# electrodePCB.net
KiCad netlist of a schematic drawn in Altium Designer
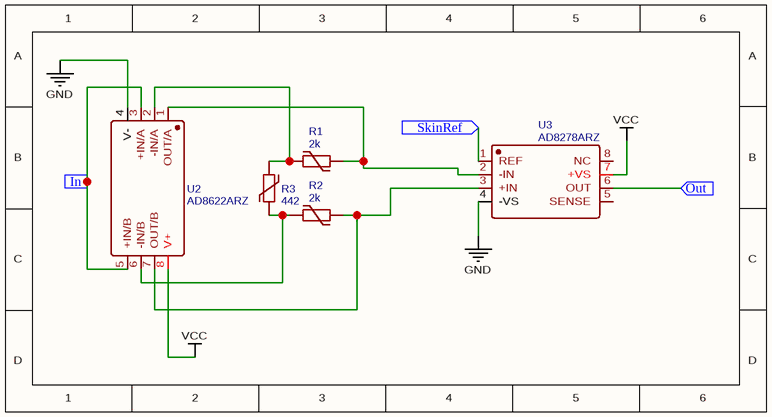
[diagram p0: electrodePCB.schdoc]

(export (version "E")
  (design (tool "Eeschema 10.0.6"))
  (components
    (comp (ref "R1")
      (value "2k")
      (fields
        (field (name "BOM_SUPPLIER PART") "C388274")
        (field (name "BOM_MANUFACTURER PART") "TCTR0402F100KF3950T")
        (field (name "CONTRIBUTOR") "LCSC")
      )
      (libsource (lib "altium-import") (part "root_0_2k_"))
    )
    (comp (ref "R2")
      (value "2k")
      (fields
        (field (name "BOM_SUPPLIER PART") "C388274")
        (field (name "BOM_MANUFACTURER PART") "TCTR0402F100KF3950T")
        (field (name "CONTRIBUTOR") "LCSC")
      )
      (libsource (lib "altium-import") (part "root_0_2k_"))
    )
    (comp (ref "R3")
      (value "442")
      (fields
        (field (name "BOM_SUPPLIER PART") "C388281")
        (field (name "BOM_MANUFACTURER PART") "TCTR0603F10K0F3980T")
        (field (name "CONTRIBUTOR") "LCSC")
      )
      (libsource (lib "altium-import") (part "root_1_442_"))
    )
    (comp (ref "U2")
      (value "AD8622ARZ")
      (fields (field (name "BOM_SUPPLIER PART") "C106970"))
      (libsource (lib "altium-import") (part "root_3_AD8622ARZ_"))
    )
    (comp (ref "U3")
      (value "AD8278ARZ")
      (fields (field (name "BOM_SUPPLIER PART") "C209371") (field (name "CONTRIBUTOR") "LCSC"))
      (libsource (lib "altium-import") (part "root_0_AD8278ARZ_"))
    )
  )
  (nets
    (net (code "1") (name "/In") (class "Default")
      (node (ref "U2") (pin "3") (pinfunction "+IN/A_3") (pintype "passive"))
      (node (ref "U2") (pin "5") (pinfunction "+IN/B_5") (pintype "passive"))
    )
    (net (code "2") (name "/Out") (class "Default")
      (node (ref "U3") (pin "6") (pinfunction "OUT_6") (pintype "passive"))
    )
    (net (code "3") (name "/SkinRef") (class "Default")
      (node (ref "U3") (pin "1") (pinfunction "REF_1") (pintype "passive"))
    )
    (net (code "4") (name "GND") (class "Default")
      (node (ref "U2") (pin "4") (pinfunction "V-_4") (pintype "passive"))
      (node (ref "U3") (pin "4") (pinfunction "-VS_4") (pintype "passive"))
    )
    (net (code "5") (name "Net-(U2--IN{slash}A)") (class "Default")
      (node (ref "R1") (pin "1") (pinfunction "1_1") (pintype "passive"))
      (node (ref "R3") (pin "2") (pinfunction "2_2") (pintype "passive"))
      (node (ref "U2") (pin "2") (pinfunction "-IN/A_2") (pintype "passive"))
    )
    (net (code "6") (name "Net-(U2--IN{slash}B)") (class "Default")
      (node (ref "R2") (pin "1") (pinfunction "1_1") (pintype "passive"))
      (node (ref "R3") (pin "1") (pinfunction "1_1") (pintype "passive"))
      (node (ref "U2") (pin "6") (pinfunction "-IN/B_6") (pintype "passive"))
    )
    (net (code "7") (name "Net-(U2-OUT{slash}A)") (class "Default")
      (node (ref "R1") (pin "2") (pinfunction "2_2") (pintype "passive"))
      (node (ref "U2") (pin "1") (pinfunction "OUT/A_1") (pintype "passive"))
      (node (ref "U3") (pin "2") (pinfunction "-IN_2") (pintype "passive"))
    )
    (net (code "8") (name "Net-(U2-OUT{slash}B)") (class "Default")
      (node (ref "R2") (pin "2") (pinfunction "2_2") (pintype "passive"))
      (node (ref "U2") (pin "7") (pinfunction "OUT/B_7") (pintype "passive"))
      (node (ref "U3") (pin "3") (pinfunction "+IN_3") (pintype "passive"))
    )
    (net (code "9") (name "VCC") (class "Default")
      (node (ref "U2") (pin "8") (pinfunction "V+_8") (pintype "passive"))
      (node (ref "U3") (pin "7") (pinfunction "+VS_7") (pintype "passive"))
    )
    (net (code "10") (name "unconnected-(U3-NC-Pad8)") (class "Default")
      (node (ref "U3") (pin "8") (pinfunction "NC_8") (pintype "passive"))
    )
    (net (code "11") (name "unconnected-(U3-SENSE-Pad5)") (class "Default")
      (node (ref "U3") (pin "5") (pinfunction "SENSE_5") (pintype "passive"))
    )
  )
)
